# DAC_ADC_MAX5841_MAX1037.net
KiCad netlist of a schematic drawn in Altium Designer
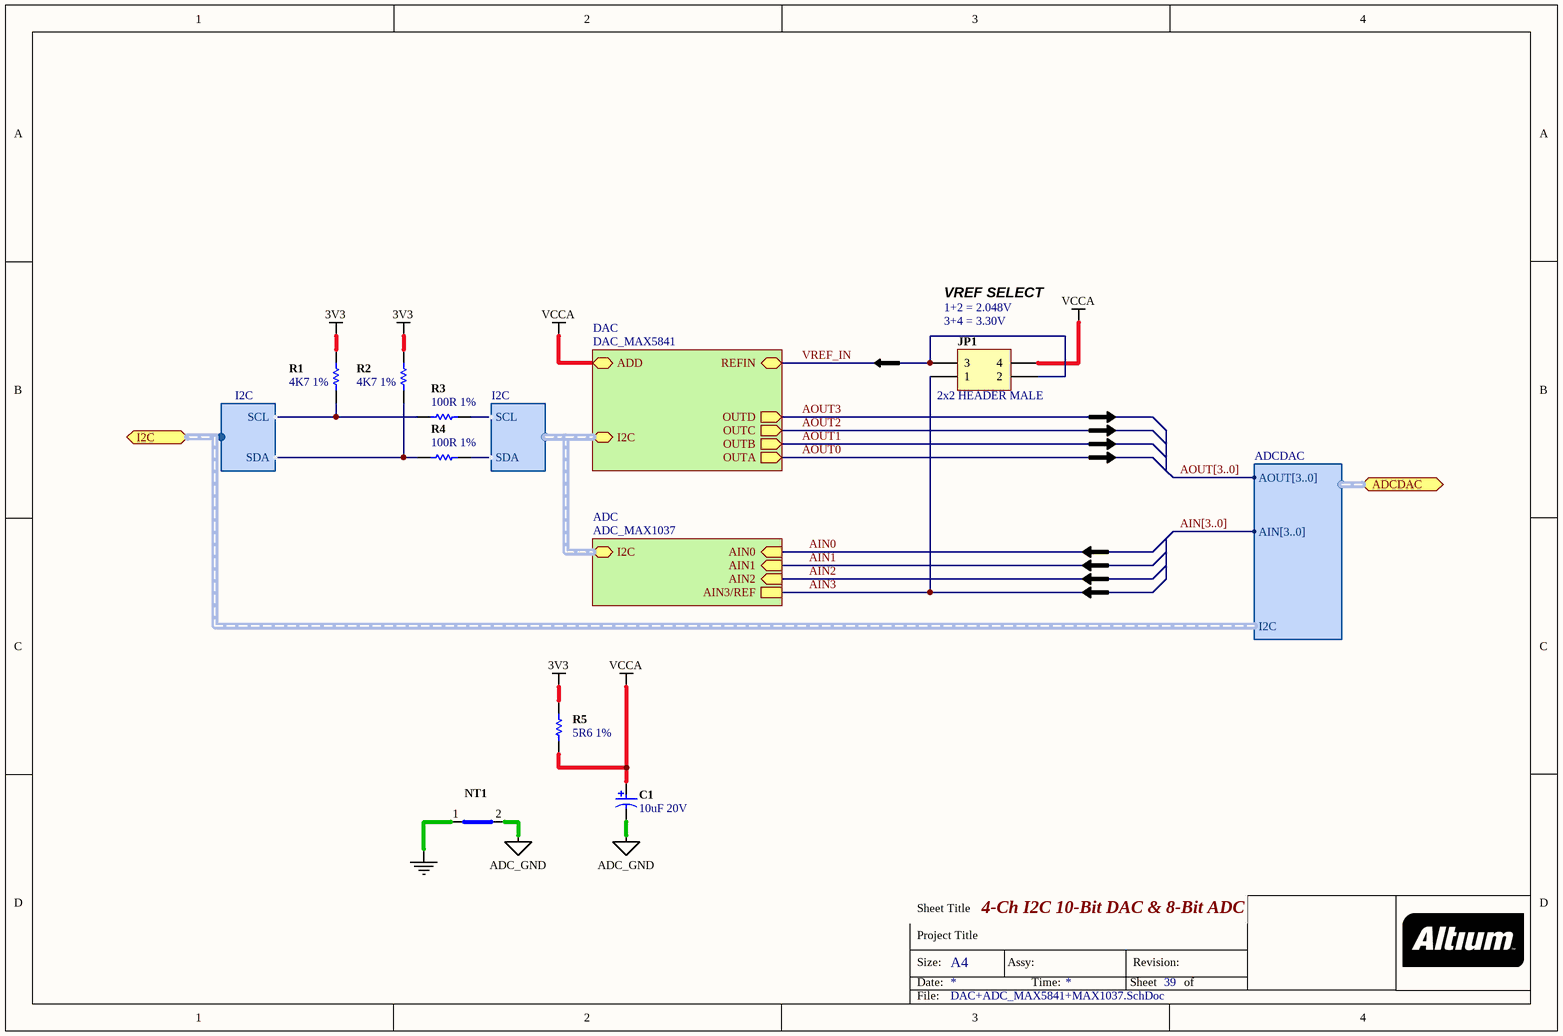
[diagram p0: DAC+ADC_MAX5841+MAX1037.SchDoc]

(export (version "E")
  (design (tool "Eeschema 10.0.6"))
  (components
    (comp (ref "C1")
      (value "10uF 20V")
      (footprint "CAPC3528-STAR")
      (description "Capacitor, Tantalum, 10uF 10% 20V MCCT-B (3528)")
      (fields (field (name "TOLERANCE") "10 %"))
      (libsource (lib "altium-import") (part "root_0_CAP-P_"))
    )
    (comp (ref "JP1")
      (value "2x2 HEADER MALE")
      (footprint "HDR2X2")
      (description "Header IDC, 2 x 2 Pin Vertical 2.54mm Pitch (Non-Boxed, Male)")
      (libsource (lib "AltiumDesignLibrary") (part "CON-HDR-2x2-STR"))
    )
    (comp (ref "NT1")
      (value "Net Tie SMT2")
      (footprint "NETTIE-SMT2-16X11")
      (description "Net-Tie, Surface Mount, 2 x 0.8mm x 0.4mm SMT Pads - For 0.4mm Track")
      (libsource (lib "AltiumDesignLibrary") (part "NETTIE-SMT2"))
    )
    (comp (ref "R1")
      (value "4K7 1%")
      (footprint "RESC1005-STAR")
      (description "Resistor, 4K7 1% 0402 (1005)")
      (fields (field (name "TOLERANCE") "1 %"))
      (libsource (lib "altium-import") (part "root_0_RES_"))
    )
    (comp (ref "R2")
      (value "4K7 1%")
      (footprint "RESC1005-STAR")
      (description "Resistor, 4K7 1% 0402 (1005)")
      (fields (field (name "TOLERANCE") "1 %"))
      (libsource (lib "altium-import") (part "root_0_RES_"))
    )
    (comp (ref "R3")
      (value "100R 1%")
      (footprint "RESC1005-STAR")
      (description "Resistor, 100R 1% 0402 (1005)")
      (fields (field (name "TOLERANCE") "1 %"))
      (libsource (lib "altium-import") (part "root_1_RES_"))
    )
    (comp (ref "R4")
      (value "100R 1%")
      (footprint "RESC1005-STAR")
      (description "Resistor, 100R 1% 0402 (1005)")
      (fields (field (name "TOLERANCE") "1 %"))
      (libsource (lib "altium-import") (part "root_1_RES_"))
    )
    (comp (ref "R5")
      (value "5R6 1%")
      (footprint "RESC1005-STAR")
      (description "Resistor, 5R6 1% 0402 (1005)")
      (fields (field (name "TOLERANCE") "1 %"))
      (libsource (lib "AltiumDesignLibrary") (part "RES"))
    )
  )
  (nets
    (net (code "7") (name "/AIN3") (class "Default")
      (node (ref "JP1") (pin "1") (pinfunction "1_1") (pintype "passive"))
    )
    (net (code "13") (name "/VREF_IN") (class "Default")
      (node (ref "JP1") (pin "2") (pinfunction "2_2") (pintype "passive"))
      (node (ref "JP1") (pin "3") (pinfunction "3_3") (pintype "passive"))
    )
    (net (code "16") (name "3V3") (class "Default")
      (node (ref "R1") (pin "1") (pinfunction "1_1") (pintype "passive"))
      (node (ref "R2") (pin "1") (pinfunction "1_1") (pintype "passive"))
      (node (ref "R5") (pin "2") (pinfunction "2_2") (pintype "passive"))
    )
    (net (code "17") (name "ADC_GND") (class "Default")
      (node (ref "C1") (pin "2") (pinfunction "2_2") (pintype "passive"))
      (node (ref "NT1") (pin "2") (pinfunction "Net2_2") (pintype "passive"))
    )
    (net (code "18") (name "GND") (class "Default")
      (node (ref "NT1") (pin "1") (pinfunction "Net1_1") (pintype "passive"))
    )
    (net (code "19") (name "Net-(R1-Pad2)") (class "Default")
      (node (ref "R1") (pin "2") (pinfunction "2_2") (pintype "passive"))
      (node (ref "R3") (pin "1") (pinfunction "1_1") (pintype "passive"))
    )
    (net (code "20") (name "Net-(R2-Pad2)") (class "Default")
      (node (ref "R2") (pin "2") (pinfunction "2_2") (pintype "passive"))
      (node (ref "R4") (pin "1") (pinfunction "1_1") (pintype "passive"))
    )
    (net (code "21") (name "VCCA") (class "Default")
      (node (ref "C1") (pin "1") (pinfunction "1_1") (pintype "passive"))
      (node (ref "JP1") (pin "4") (pinfunction "4_4") (pintype "passive"))
      (node (ref "R5") (pin "1") (pinfunction "1_1") (pintype "passive"))
    )
    (net (code "22") (name "unconnected-(R3-Pad2)") (class "Default")
      (node (ref "R3") (pin "2") (pinfunction "2_2") (pintype "passive"))
    )
    (net (code "23") (name "unconnected-(R4-Pad2)") (class "Default")
      (node (ref "R4") (pin "2") (pinfunction "2_2") (pintype "passive"))
    )
  )
)
